# Gateway.net
KiCad netlist of a schematic drawn in EAGLE
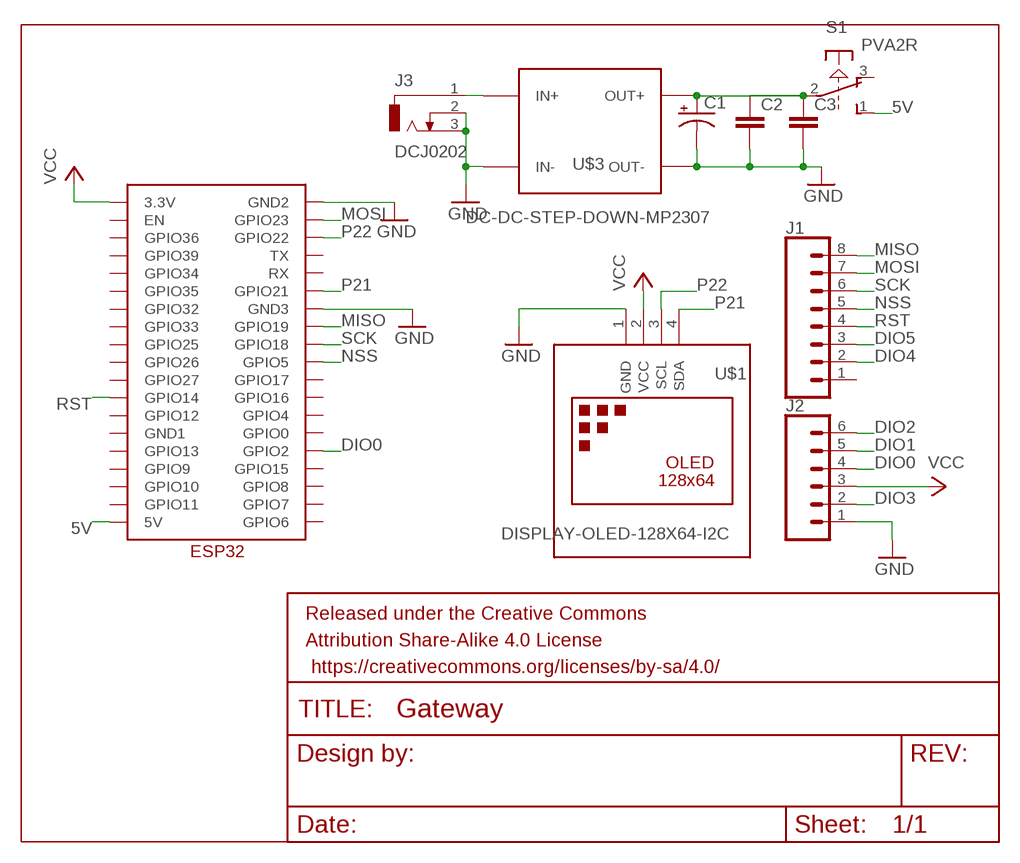
[diagram p0: schematic, sheet 1]

(export (version "E")
  (design (tool "Eeschema 10.0.6"))
  (components
    (comp (ref "C1")
      (value "CPOL-USE2,5-6E")
      (footprint "eagle-import:E2,5-6E")
      (libsource (lib "eagle-import") (part "CPOL-USE2,5-6E"))
    )
    (comp (ref "C2")
      (value "C-EUC1206")
      (footprint "eagle-import:C1206")
      (libsource (lib "eagle-import") (part "C-EUC1206"))
    )
    (comp (ref "C3")
      (value "C-EUC1206")
      (footprint "eagle-import:C1206")
      (libsource (lib "eagle-import") (part "C-EUC1206"))
    )
    (comp (ref "FRAME1")
      (value "FRAME-LEDGER")
      (footprint "eagle-import:CREATIVE_COMMONS")
      (libsource (lib "eagle-import") (part "FRAME-LEDGER"))
    )
    (comp (ref "J1")
      (value "CONN_08\"")
      (footprint "eagle-import:1X08")
      (libsource (lib "eagle-import") (part "CONN_08{dblquote}"))
    )
    (comp (ref "J2")
      (value "CONN_06SILK_FEMALE_PTH")
      (footprint "eagle-import:1X06")
      (libsource (lib "eagle-import") (part "CONN_06SILK_FEMALE_PTH"))
    )
    (comp (ref "J3")
      (value "DCJ0202")
      (footprint "eagle-import:DCJ0202")
      (libsource (lib "eagle-import") (part "DCJ0202"))
    )
    (comp (ref "S1")
      (value "PVA2R")
      (footprint "eagle-import:PVA2R")
      (libsource (lib "eagle-import") (part "PVA2R"))
    )
    (comp (ref "U$1")
      (value "DISPLAY-OLED-128X64-I2C")
      (footprint "eagle-import:DISPLAY-OLED-128X64-I2C")
      (libsource (lib "eagle-import") (part "DISPLAY-OLED-128X64-I2C"))
    )
    (comp (ref "U$2")
      (value "ESP32")
      (footprint "eagle-import:ESP32")
      (libsource (lib "eagle-import") (part "ESP32"))
    )
    (comp (ref "U$3")
      (value "DC-DC-STEP-DOWN-MP2307")
      (footprint "eagle-import:DC-DC-STEP-DOWN-MP2307")
      (libsource (lib "eagle-import") (part "DC-DC-STEP-DOWN-MP2307"))
    )
  )
  (nets
    (net (code "1") (name "/5V") (class "Default")
      (node (ref "S1") (pin "1") (pinfunction "S_1") (pintype "passive"))
      (node (ref "U$2") (pin "5V") (pinfunction "5V_5V") (pintype "bidirectional"))
    )
    (net (code "2") (name "/DIO0") (class "Default")
      (node (ref "J2") (pin "4") (pinfunction "4_4") (pintype "passive"))
      (node (ref "U$2") (pin "GPIO2") (pinfunction "GPIO2_GPIO2") (pintype "bidirectional"))
    )
    (net (code "3") (name "/DIO1") (class "Default")
      (node (ref "J2") (pin "5") (pinfunction "5_5") (pintype "passive"))
    )
    (net (code "4") (name "/DIO2") (class "Default")
      (node (ref "J2") (pin "6") (pinfunction "6_6") (pintype "passive"))
    )
    (net (code "5") (name "/DIO3") (class "Default")
      (node (ref "J2") (pin "2") (pinfunction "2_2") (pintype "passive"))
    )
    (net (code "6") (name "/DIO4") (class "Default")
      (node (ref "J1") (pin "2") (pinfunction "2_2") (pintype "passive"))
    )
    (net (code "7") (name "/DIO5") (class "Default")
      (node (ref "J1") (pin "3") (pinfunction "3_3") (pintype "passive"))
    )
    (net (code "8") (name "/MISO") (class "Default")
      (node (ref "J1") (pin "8") (pinfunction "8_8") (pintype "passive"))
      (node (ref "U$2") (pin "GPIO19") (pinfunction "GPIO19_GPIO19") (pintype "bidirectional"))
    )
    (net (code "9") (name "/MOSI") (class "Default")
      (node (ref "J1") (pin "7") (pinfunction "7_7") (pintype "passive"))
      (node (ref "U$2") (pin "GPIO23") (pinfunction "GPIO23_GPIO23") (pintype "bidirectional"))
    )
    (net (code "10") (name "/NSS") (class "Default")
      (node (ref "J1") (pin "5") (pinfunction "5_5") (pintype "passive"))
      (node (ref "U$2") (pin "GPIO5") (pinfunction "GPIO5_GPIO5") (pintype "bidirectional"))
    )
    (net (code "11") (name "/P21") (class "Default")
      (node (ref "U$1") (pin "4") (pinfunction "SDA_4") (pintype "bidirectional"))
      (node (ref "U$2") (pin "GPIO21") (pinfunction "GPIO21_GPIO21") (pintype "bidirectional"))
    )
    (net (code "12") (name "/P22") (class "Default")
      (node (ref "U$1") (pin "3") (pinfunction "SCL_3") (pintype "bidirectional"))
      (node (ref "U$2") (pin "GPIO22") (pinfunction "GPIO22_GPIO22") (pintype "bidirectional"))
    )
    (net (code "13") (name "/RST") (class "Default")
      (node (ref "J1") (pin "4") (pinfunction "4_4") (pintype "passive"))
      (node (ref "U$2") (pin "GPIO14") (pinfunction "GPIO14_GPIO14") (pintype "bidirectional"))
    )
    (net (code "14") (name "/SCK") (class "Default")
      (node (ref "J1") (pin "6") (pinfunction "6_6") (pintype "passive"))
      (node (ref "U$2") (pin "GPIO18") (pinfunction "GPIO18_GPIO18") (pintype "bidirectional"))
    )
    (net (code "15") (name "GND") (class "Default")
      (node (ref "C1") (pin "-") (pinfunction "-_-") (pintype "passive"))
      (node (ref "C2") (pin "2") (pinfunction "2_2") (pintype "passive"))
      (node (ref "C3") (pin "2") (pinfunction "2_2") (pintype "passive"))
      (node (ref "J2") (pin "1") (pinfunction "1_1") (pintype "passive"))
      (node (ref "J3") (pin "2") (pinfunction "2_2") (pintype "passive"))
      (node (ref "J3") (pin "3") (pinfunction "3_3") (pintype "passive"))
      (node (ref "U$1") (pin "1") (pinfunction "GND_1") (pintype "power_in"))
      (node (ref "U$2") (pin "GND2") (pinfunction "GND2_GND2") (pintype "bidirectional"))
      (node (ref "U$2") (pin "GND3") (pinfunction "GND3_GND3") (pintype "bidirectional"))
      (node (ref "U$3") (pin "IN-") (pinfunction "IN-_IN-") (pintype "bidirectional"))
      (node (ref "U$3") (pin "OUT-") (pinfunction "OUT-_OUT-") (pintype "bidirectional"))
    )
    (net (code "16") (name "Net-(J3-Pad1)") (class "Default")
      (node (ref "J3") (pin "1") (pinfunction "1_1") (pintype "passive"))
      (node (ref "U$3") (pin "IN+") (pinfunction "IN+_IN+") (pintype "bidirectional"))
    )
    (net (code "17") (name "Net-(S1A-P)") (class "Default")
      (node (ref "C1") (pin "+") (pinfunction "+_+") (pintype "passive"))
      (node (ref "C2") (pin "1") (pinfunction "1_1") (pintype "passive"))
      (node (ref "C3") (pin "1") (pinfunction "1_1") (pintype "passive"))
      (node (ref "S1") (pin "2") (pinfunction "P_2") (pintype "passive"))
      (node (ref "U$3") (pin "OUT+") (pinfunction "OUT+_OUT+") (pintype "bidirectional"))
    )
    (net (code "18") (name "VCC") (class "Default")
      (node (ref "J2") (pin "3") (pinfunction "3_3") (pintype "passive"))
      (node (ref "U$1") (pin "2") (pinfunction "VCC_2") (pintype "power_in"))
      (node (ref "U$2") (pin "3.3V") (pinfunction "3.3V_3.3V") (pintype "bidirectional"))
    )
    (net (code "19") (name "unconnected-(J1-Pad1)") (class "Default")
      (node (ref "J1") (pin "1") (pinfunction "1_1") (pintype "passive"))
    )
    (net (code "20") (name "unconnected-(S1A-O-Pad3)") (class "Default")
      (node (ref "S1") (pin "3") (pinfunction "O_3") (pintype "passive"))
    )
    (net (code "21") (name "unconnected-(U$2-PadEN)") (class "Default")
      (node (ref "U$2") (pin "EN") (pinfunction "EN_EN") (pintype "bidirectional"))
    )
    (net (code "22") (name "unconnected-(U$2-PadGND1)") (class "Default")
      (node (ref "U$2") (pin "GND1") (pinfunction "GND1_GND1") (pintype "bidirectional"))
    )
    (net (code "23") (name "unconnected-(U$2-PadGPIO0)") (class "Default")
      (node (ref "U$2") (pin "GPIO0") (pinfunction "GPIO0_GPIO0") (pintype "bidirectional"))
    )
    (net (code "24") (name "unconnected-(U$2-PadGPIO4)") (class "Default")
      (node (ref "U$2") (pin "GPIO4") (pinfunction "GPIO4_GPIO4") (pintype "bidirectional"))
    )
    (net (code "25") (name "unconnected-(U$2-PadGPIO6)") (class "Default")
      (node (ref "U$2") (pin "GPIO6") (pinfunction "GPIO6_GPIO6") (pintype "bidirectional"))
    )
    (net (code "26") (name "unconnected-(U$2-PadGPIO7)") (class "Default")
      (node (ref "U$2") (pin "GPIO7") (pinfunction "GPIO7_GPIO7") (pintype "bidirectional"))
    )
    (net (code "27") (name "unconnected-(U$2-PadGPIO8)") (class "Default")
      (node (ref "U$2") (pin "GPIO8") (pinfunction "GPIO8_GPIO8") (pintype "bidirectional"))
    )
    (net (code "28") (name "unconnected-(U$2-PadGPIO9)") (class "Default")
      (node (ref "U$2") (pin "GPIO9") (pinfunction "GPIO9_GPIO9") (pintype "bidirectional"))
    )
    (net (code "29") (name "unconnected-(U$2-PadGPIO10)") (class "Default")
      (node (ref "U$2") (pin "GPIO10") (pinfunction "GPIO10_GPIO10") (pintype "bidirectional"))
    )
    (net (code "30") (name "unconnected-(U$2-PadGPIO11)") (class "Default")
      (node (ref "U$2") (pin "GPIO11") (pinfunction "GPIO11_GPIO11") (pintype "bidirectional"))
    )
    (net (code "31") (name "unconnected-(U$2-PadGPIO12)") (class "Default")
      (node (ref "U$2") (pin "GPIO12") (pinfunction "GPIO12_GPIO12") (pintype "bidirectional"))
    )
    (net (code "32") (name "unconnected-(U$2-PadGPIO13)") (class "Default")
      (node (ref "U$2") (pin "GPIO13") (pinfunction "GPIO13_GPIO13") (pintype "bidirectional"))
    )
    (net (code "33") (name "unconnected-(U$2-PadGPIO15)") (class "Default")
      (node (ref "U$2") (pin "GPIO15") (pinfunction "GPIO15_GPIO15") (pintype "bidirectional"))
    )
    (net (code "34") (name "unconnected-(U$2-PadGPIO16)") (class "Default")
      (node (ref "U$2") (pin "GPIO16") (pinfunction "GPIO16_GPIO16") (pintype "bidirectional"))
    )
    (net (code "35") (name "unconnected-(U$2-PadGPIO17)") (class "Default")
      (node (ref "U$2") (pin "GPIO17") (pinfunction "GPIO17_GPIO17") (pintype "bidirectional"))
    )
    (net (code "36") (name "unconnected-(U$2-PadGPIO25)") (class "Default")
      (node (ref "U$2") (pin "GPIO25") (pinfunction "GPIO25_GPIO25") (pintype "bidirectional"))
    )
    (net (code "37") (name "unconnected-(U$2-PadGPIO26)") (class "Default")
      (node (ref "U$2") (pin "GPIO26") (pinfunction "GPIO26_GPIO26") (pintype "bidirectional"))
    )
    (net (code "38") (name "unconnected-(U$2-PadGPIO27)") (class "Default")
      (node (ref "U$2") (pin "GPIO27") (pinfunction "GPIO27_GPIO27") (pintype "bidirectional"))
    )
    (net (code "39") (name "unconnected-(U$2-PadGPIO32)") (class "Default")
      (node (ref "U$2") (pin "GPIO32") (pinfunction "GPIO32_GPIO32") (pintype "bidirectional"))
    )
    (net (code "40") (name "unconnected-(U$2-PadGPIO33)") (class "Default")
      (node (ref "U$2") (pin "GPIO33") (pinfunction "GPIO33_GPIO33") (pintype "bidirectional"))
    )
    (net (code "41") (name "unconnected-(U$2-PadGPIO34)") (class "Default")
      (node (ref "U$2") (pin "GPIO34") (pinfunction "GPIO34_GPIO34") (pintype "bidirectional"))
    )
    (net (code "42") (name "unconnected-(U$2-PadGPIO35)") (class "Default")
      (node (ref "U$2") (pin "GPIO35") (pinfunction "GPIO35_GPIO35") (pintype "bidirectional"))
    )
    (net (code "43") (name "unconnected-(U$2-PadGPIO36)") (class "Default")
      (node (ref "U$2") (pin "GPIO36") (pinfunction "GPIO36_GPIO36") (pintype "bidirectional"))
    )
    (net (code "44") (name "unconnected-(U$2-PadGPIO39)") (class "Default")
      (node (ref "U$2") (pin "GPIO39") (pinfunction "GPIO39_GPIO39") (pintype "bidirectional"))
    )
    (net (code "45") (name "unconnected-(U$2-PadRX)") (class "Default")
      (node (ref "U$2") (pin "RX") (pinfunction "RX_RX") (pintype "bidirectional"))
    )
    (net (code "46") (name "unconnected-(U$2-PadTX)") (class "Default")
      (node (ref "U$2") (pin "TX") (pinfunction "TX_TX") (pintype "bidirectional"))
    )
  )
)
